# FLYTE-v1.net
KiCad netlist of a schematic drawn in EAGLE
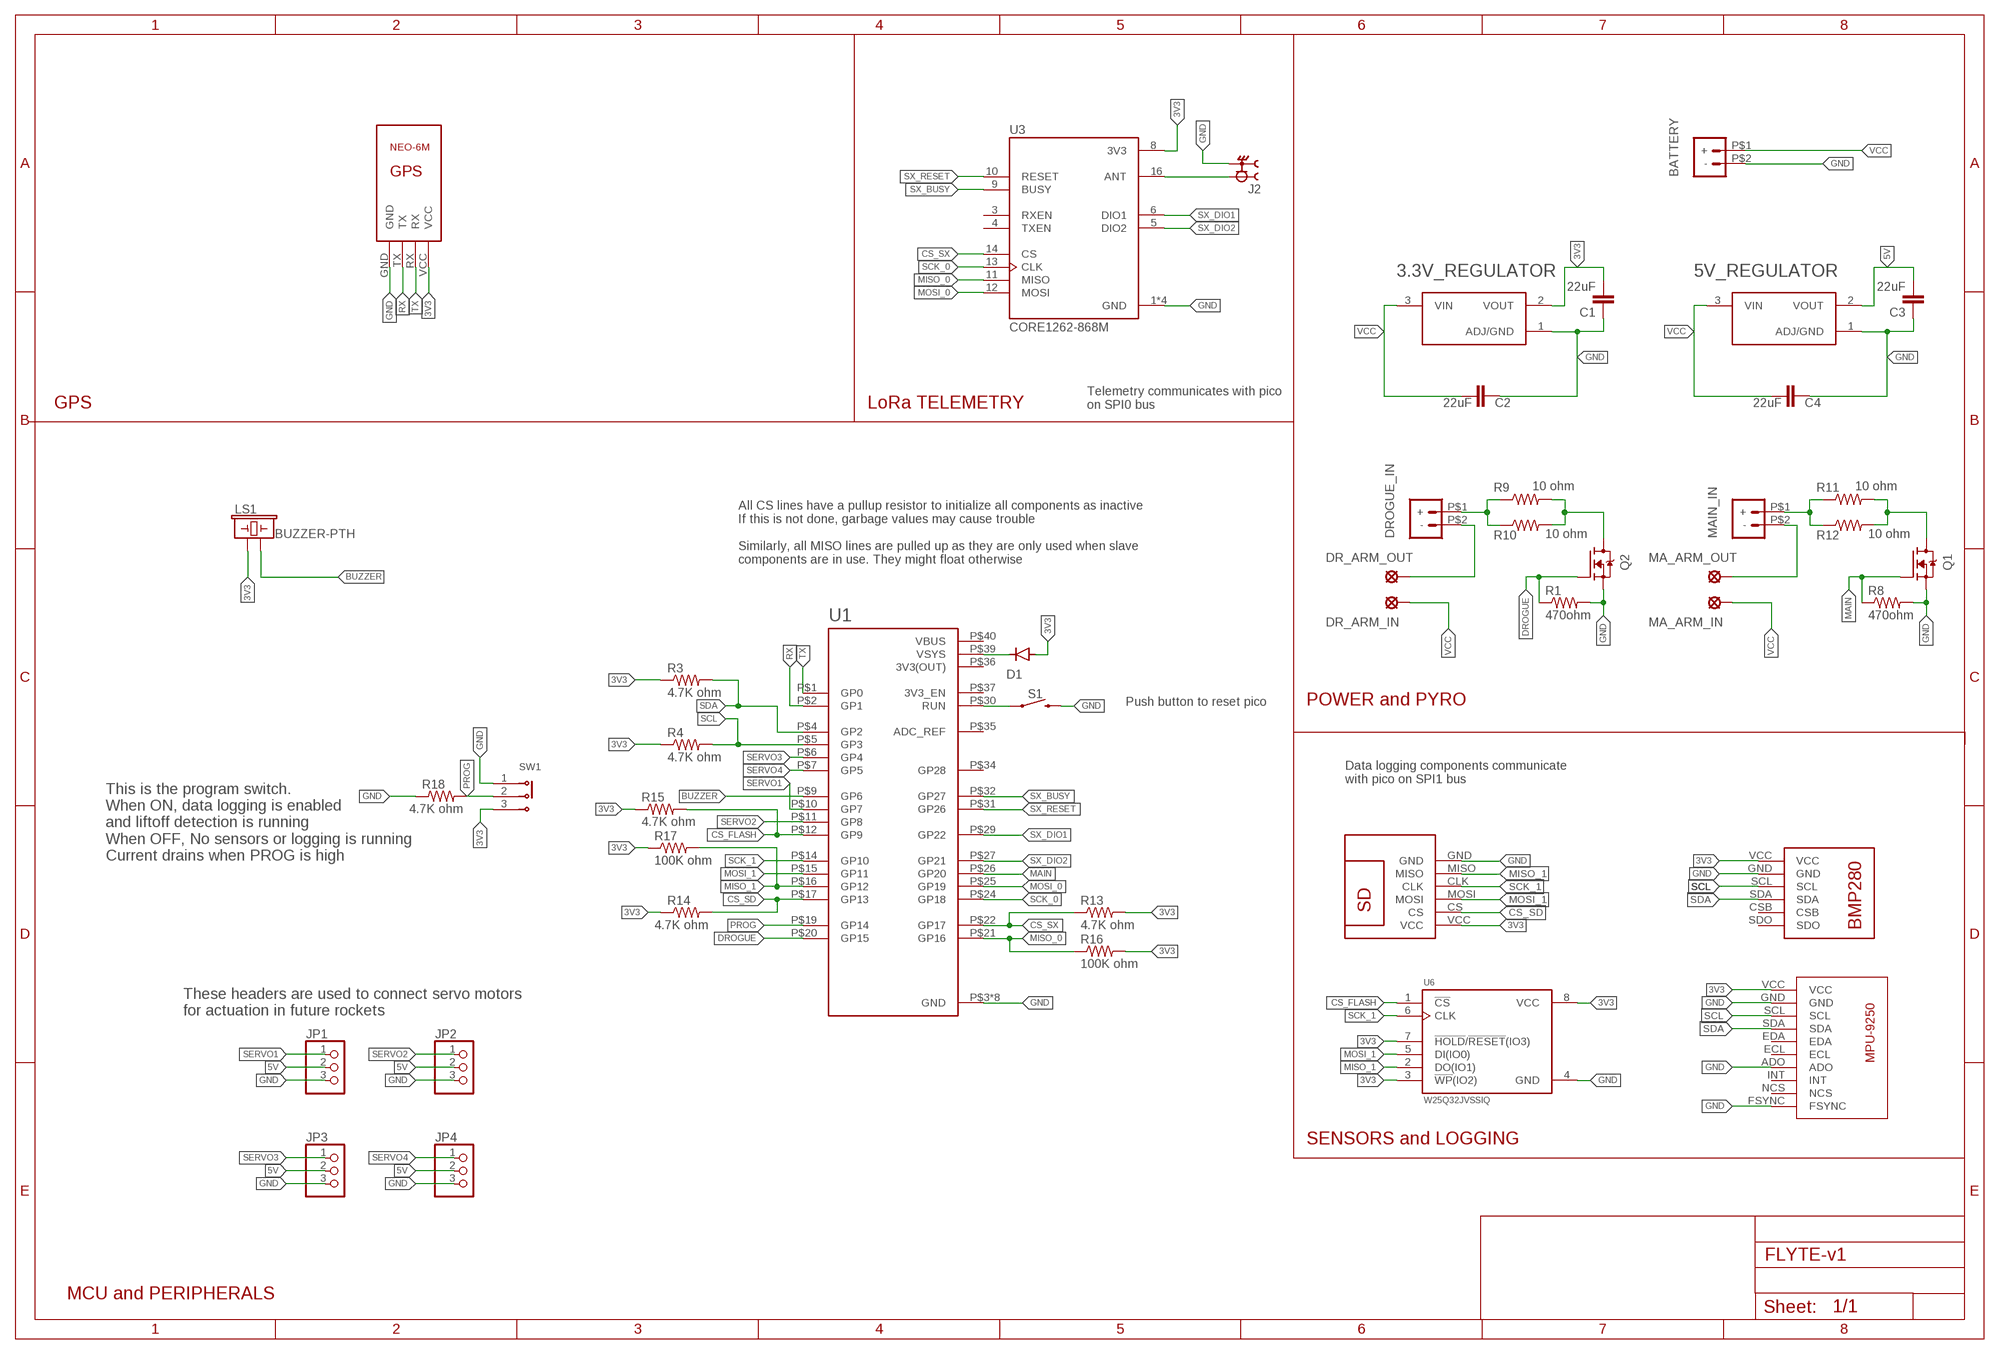
[diagram p0: schematic, sheet 1]

(export (version "E")
  (design (tool "Eeschema 10.0.6"))
  (components
    (comp (ref "3.3V_REGULATOR")
      (value "AMS1117-3.3")
      (footprint "eagle-import:SOT229P700X180-4N")
      (fields (field (name "MF") "Advanced Monolithic Systems"))
      (libsource (lib "eagle-import") (part "AMS1117-3.3"))
    )
    (comp (ref "5V_REGULATOR")
      (value "AMS1117-3.3")
      (footprint "eagle-import:SOT229P700X180-4N")
      (fields (field (name "MF") "Advanced Monolithic Systems"))
      (libsource (lib "eagle-import") (part "AMS1117-3.3"))
    )
    (comp (ref "BATTERY")
      (value "XT30UPB-M")
      (footprint "eagle-import:XT30UPB-M")
      (fields (field (name "MF") "amass"))
      (libsource (lib "eagle-import") (part "XT30UPB-M"))
    )
    (comp (ref "C1")
      (value "22uF")
      (footprint "eagle-import:0805")
      (libsource (lib "eagle-import") (part "22UF-0805-6.3V-20%"))
    )
    (comp (ref "C2")
      (value "22uF")
      (footprint "eagle-import:0805")
      (libsource (lib "eagle-import") (part "22UF-0805-6.3V-20%"))
    )
    (comp (ref "C3")
      (value "22uF")
      (footprint "eagle-import:0805")
      (libsource (lib "eagle-import") (part "22UF-0805-6.3V-20%"))
    )
    (comp (ref "C4")
      (value "22uF")
      (footprint "eagle-import:0805")
      (libsource (lib "eagle-import") (part "22UF-0805-6.3V-20%"))
    )
    (comp (ref "D1")
      (value "1N4004")
      (footprint "eagle-import:DO41-10")
      (libsource (lib "eagle-import") (part "1N4004"))
    )
    (comp (ref "DROGUE_IN")
      (value "XT30UPB-M")
      (footprint "eagle-import:XT30UPB-M")
      (fields (field (name "MF") "amass"))
      (libsource (lib "eagle-import") (part "XT30UPB-M"))
    )
    (comp (ref "DR_ARM_IN")
      (value "LSP10")
      (footprint "eagle-import:LSP10")
      (libsource (lib "eagle-import") (part "LSP10"))
    )
    (comp (ref "DR_ARM_OUT")
      (value "LSP10")
      (footprint "eagle-import:LSP10")
      (libsource (lib "eagle-import") (part "LSP10"))
    )
    (comp (ref "J2")
      (value "CONSMA002")
      (footprint "eagle-import:LINX_CONSMA002")
      (fields (field (name "MF") "Linx"))
      (libsource (lib "eagle-import") (part "CONSMA002"))
    )
    (comp (ref "JP1")
      (value "PINHD-1X3")
      (footprint "eagle-import:1X03")
      (libsource (lib "eagle-import") (part "PINHD-1X3"))
    )
    (comp (ref "JP2")
      (value "PINHD-1X3")
      (footprint "eagle-import:1X03")
      (libsource (lib "eagle-import") (part "PINHD-1X3"))
    )
    (comp (ref "JP3")
      (value "PINHD-1X3")
      (footprint "eagle-import:1X03")
      (libsource (lib "eagle-import") (part "PINHD-1X3"))
    )
    (comp (ref "JP4")
      (value "PINHD-1X3")
      (footprint "eagle-import:1X03")
      (libsource (lib "eagle-import") (part "PINHD-1X3"))
    )
    (comp (ref "LS1")
      (value "BUZZER-PTH")
      (footprint "eagle-import:BUZZER-12MM")
      (libsource (lib "eagle-import") (part "BUZZER-PTH"))
    )
    (comp (ref "MAIN_IN")
      (value "XT30UPB-M")
      (footprint "eagle-import:XT30UPB-M")
      (fields (field (name "MF") "amass"))
      (libsource (lib "eagle-import") (part "XT30UPB-M"))
    )
    (comp (ref "MA_ARM_IN")
      (value "LSP10")
      (footprint "eagle-import:LSP10")
      (libsource (lib "eagle-import") (part "LSP10"))
    )
    (comp (ref "MA_ARM_OUT")
      (value "LSP10")
      (footprint "eagle-import:LSP10")
      (libsource (lib "eagle-import") (part "LSP10"))
    )
    (comp (ref "Q1")
      (value "IRF540NPBF")
      (footprint "eagle-import:TO254P1054X469X1930-3")
      (fields (field (name "MF") "Infineon"))
      (libsource (lib "eagle-import") (part "IRF540NPBF"))
    )
    (comp (ref "Q2")
      (value "IRF540NPBF")
      (footprint "eagle-import:TO254P1054X469X1930-3")
      (fields (field (name "MF") "Infineon"))
      (libsource (lib "eagle-import") (part "IRF540NPBF"))
    )
    (comp (ref "R1")
      (value "470ohm")
      (footprint "eagle-import:R0805")
      (libsource (lib "eagle-import") (part "R-US_R0805"))
    )
    (comp (ref "R3")
      (value "4.7K ohm")
      (footprint "eagle-import:R0805")
      (libsource (lib "eagle-import") (part "R-US_R0805"))
    )
    (comp (ref "R4")
      (value "4.7K ohm")
      (footprint "eagle-import:R0805")
      (libsource (lib "eagle-import") (part "R-US_R0805"))
    )
    (comp (ref "R8")
      (value "470ohm")
      (footprint "eagle-import:R0805")
      (libsource (lib "eagle-import") (part "R-US_R0805"))
    )
    (comp (ref "R9")
      (value "10 ohm")
      (footprint "eagle-import:0207_10")
      (libsource (lib "eagle-import") (part "R-US_0207/10"))
    )
    (comp (ref "R10")
      (value "10 ohm")
      (footprint "eagle-import:0207_10")
      (libsource (lib "eagle-import") (part "R-US_0207/10"))
    )
    (comp (ref "R11")
      (value "10 ohm")
      (footprint "eagle-import:0207_10")
      (libsource (lib "eagle-import") (part "R-US_0207/10"))
    )
    (comp (ref "R12")
      (value "10 ohm")
      (footprint "eagle-import:0207_10")
      (libsource (lib "eagle-import") (part "R-US_0207/10"))
    )
    (comp (ref "R13")
      (value "4.7K ohm")
      (footprint "eagle-import:R0805")
      (libsource (lib "eagle-import") (part "R-US_R0805"))
    )
    (comp (ref "R14")
      (value "4.7K ohm")
      (footprint "eagle-import:R0805")
      (libsource (lib "eagle-import") (part "R-US_R0805"))
    )
    (comp (ref "R15")
      (value "4.7K ohm")
      (footprint "eagle-import:R0805")
      (libsource (lib "eagle-import") (part "R-US_R0805"))
    )
    (comp (ref "R16")
      (value "100K ohm")
      (footprint "eagle-import:R0805")
      (libsource (lib "eagle-import") (part "R-US_R0805"))
    )
    (comp (ref "R17")
      (value "100K ohm")
      (footprint "eagle-import:R0805")
      (libsource (lib "eagle-import") (part "R-US_R0805"))
    )
    (comp (ref "R18")
      (value "4.7K ohm")
      (footprint "eagle-import:R0805")
      (libsource (lib "eagle-import") (part "R-US_R0805"))
    )
    (comp (ref "S1")
      (value "MOMENTARY-SWITCH-SPST-PTH-6.0MM")
      (footprint "eagle-import:TACTILE_SWITCH_PTH_6.0MM")
      (libsource (lib "eagle-import") (part "MOMENTARY-SWITCH-SPST-PTH-6.0MM"))
    )
    (comp (ref "SW1")
      (value "1825159-1")
      (footprint "eagle-import:SW_1825159-1")
      (fields (field (name "MF") "TE Connectivity"))
      (libsource (lib "eagle-import") (part "1825159-1"))
    )
    (comp (ref "U$1")
      (value "BMP280")
      (footprint "eagle-import:BMP280")
      (libsource (lib "eagle-import") (part "BMP280"))
    )
    (comp (ref "U$2")
      (value "GY-9250")
      (footprint "eagle-import:GY-9250")
      (libsource (lib "eagle-import") (part "GY-9250"))
    )
    (comp (ref "U$3")
      (value "SDREADER")
      (footprint "eagle-import:SDREADER")
      (libsource (lib "eagle-import") (part "SDREADER"))
    )
    (comp (ref "U$4")
      (value "NEO-6M")
      (footprint "eagle-import:NEO-6M")
      (libsource (lib "eagle-import") (part "NEO-6M"))
    )
    (comp (ref "U1")
      (value "RASPBERRY_PICO-NO_DEBUG")
      (footprint "eagle-import:PICO-PKG-NO_DEBUG")
      (libsource (lib "eagle-import") (part "RASPBERRY_PICO-NO_DEBUG"))
    )
    (comp (ref "U3")
      (value "CORE1262-868M")
      (footprint "eagle-import:XCVR_CORE1262-868M")
      (fields (field (name "MF") "Waveshare Electronics") (field (name "MP") "Core1262-868M"))
      (libsource (lib "eagle-import") (part "CORE1262-868M"))
    )
    (comp (ref "U6")
      (value "W25Q32JVSSIQ")
      (footprint "eagle-import:SOIC127P790X216-8N")
      (fields (field (name "MF") "Winbond"))
      (libsource (lib "eagle-import") (part "W25Q32JVSSIQ"))
    )
  )
  (nets
    (net (code "1") (name "/3V3(OUT)") (class "Default")
      (node (ref "U1") (pin "P$36") (pinfunction "3V3(OUT)_P$36") (pintype "power_in"))
    )
    (net (code "2") (name "/VBUS") (class "Default")
      (node (ref "U1") (pin "P$40") (pinfunction "VBUS_P$40") (pintype "power_in"))
    )
    (net (code "3") (name "3V3") (class "Default")
      (node (ref "3.3V_REGULATOR") (pin "2") (pinfunction "VOUT_2") (pintype "output"))
      (node (ref "C1") (pin "2") (pinfunction "2_2") (pintype "passive"))
      (node (ref "D1") (pin "A") (pinfunction "A_A") (pintype "passive"))
      (node (ref "LS1") (pin "+") (pinfunction "1_+") (pintype "passive"))
      (node (ref "R13") (pin "2") (pinfunction "2_2") (pintype "passive"))
      (node (ref "R14") (pin "1") (pinfunction "1_1") (pintype "passive"))
      (node (ref "R15") (pin "1") (pinfunction "1_1") (pintype "passive"))
      (node (ref "R16") (pin "2") (pinfunction "2_2") (pintype "passive"))
      (node (ref "R17") (pin "1") (pinfunction "1_1") (pintype "passive"))
      (node (ref "R3") (pin "1") (pinfunction "1_1") (pintype "passive"))
      (node (ref "R4") (pin "1") (pinfunction "1_1") (pintype "passive"))
      (node (ref "SW1") (pin "3") (pinfunction "3_3") (pintype "passive"))
      (node (ref "U$1") (pin "VCC") (pinfunction "VCC_VCC") (pintype "bidirectional"))
      (node (ref "U$2") (pin "VCC") (pinfunction "VCC_VCC") (pintype "bidirectional"))
      (node (ref "U$3") (pin "VCC") (pinfunction "VCC_VCC") (pintype "bidirectional"))
      (node (ref "U$4") (pin "VCC") (pinfunction "VCC_VCC") (pintype "bidirectional"))
      (node (ref "U3") (pin "8") (pinfunction "3V3_8") (pintype "power_in"))
      (node (ref "U6") (pin "3") (pinfunction "~{WP}(IO2)_3") (pintype "bidirectional"))
      (node (ref "U6") (pin "7") (pinfunction "~{HOLD}/~{RESET}(IO3)_7") (pintype "bidirectional"))
      (node (ref "U6") (pin "8") (pinfunction "VCC_8") (pintype "power_in"))
    )
    (net (code "4") (name "5V") (class "Default")
      (node (ref "5V_REGULATOR") (pin "2") (pinfunction "VOUT_2") (pintype "output"))
      (node (ref "C3") (pin "2") (pinfunction "2_2") (pintype "passive"))
      (node (ref "JP1") (pin "2") (pinfunction "2_2") (pintype "passive"))
      (node (ref "JP2") (pin "2") (pinfunction "2_2") (pintype "passive"))
      (node (ref "JP3") (pin "2") (pinfunction "2_2") (pintype "passive"))
      (node (ref "JP4") (pin "2") (pinfunction "2_2") (pintype "passive"))
    )
    (net (code "5") (name "BUZZER") (class "Default")
      (node (ref "LS1") (pin "-") (pinfunction "2_-") (pintype "passive"))
      (node (ref "U1") (pin "P$9") (pinfunction "GP6_P$9") (pintype "bidirectional"))
    )
    (net (code "6") (name "CS_FLASH") (class "Default")
      (node (ref "R15") (pin "2") (pinfunction "2_2") (pintype "passive"))
      (node (ref "U1") (pin "P$12") (pinfunction "GP9_P$12") (pintype "bidirectional"))
      (node (ref "U6") (pin "1") (pinfunction "~{CS}_1") (pintype "input"))
    )
    (net (code "7") (name "CS_SD") (class "Default")
      (node (ref "R14") (pin "2") (pinfunction "2_2") (pintype "passive"))
      (node (ref "U$3") (pin "CS") (pinfunction "CS_CS") (pintype "bidirectional"))
      (node (ref "U1") (pin "P$17") (pinfunction "GP13_P$17") (pintype "bidirectional"))
    )
    (net (code "8") (name "CS_SX") (class "Default")
      (node (ref "R13") (pin "1") (pinfunction "1_1") (pintype "passive"))
      (node (ref "U1") (pin "P$22") (pinfunction "GP17_P$22") (pintype "bidirectional"))
      (node (ref "U3") (pin "14") (pinfunction "CS_14") (pintype "input"))
    )
    (net (code "9") (name "DROGUE") (class "Default")
      (node (ref "Q2") (pin "1") (pinfunction "G_1") (pintype "passive"))
      (node (ref "R1") (pin "1") (pinfunction "1_1") (pintype "passive"))
      (node (ref "U1") (pin "P$20") (pinfunction "GP15_P$20") (pintype "bidirectional"))
    )
    (net (code "10") (name "GND") (class "Default")
      (node (ref "3.3V_REGULATOR") (pin "1") (pinfunction "ADJ/GND_1") (pintype "power_in"))
      (node (ref "5V_REGULATOR") (pin "1") (pinfunction "ADJ/GND_1") (pintype "power_in"))
      (node (ref "BATTERY") (pin "P$2") (pinfunction "-_P$2") (pintype "passive"))
      (node (ref "C1") (pin "1") (pinfunction "1_1") (pintype "passive"))
      (node (ref "C2") (pin "1") (pinfunction "1_1") (pintype "passive"))
      (node (ref "C3") (pin "1") (pinfunction "1_1") (pintype "passive"))
      (node (ref "C4") (pin "1") (pinfunction "1_1") (pintype "passive"))
      (node (ref "J2") (pin "S1") (pinfunction "2_S1") (pintype "passive"))
      (node (ref "J2") (pin "S2") (pinfunction "2_S2") (pintype "passive"))
      (node (ref "J2") (pin "S3") (pinfunction "2_S3") (pintype "passive"))
      (node (ref "J2") (pin "S4") (pinfunction "2_S4") (pintype "passive"))
      (node (ref "JP1") (pin "3") (pinfunction "3_3") (pintype "passive"))
      (node (ref "JP2") (pin "3") (pinfunction "3_3") (pintype "passive"))
      (node (ref "JP3") (pin "3") (pinfunction "3_3") (pintype "passive"))
      (node (ref "JP4") (pin "3") (pinfunction "3_3") (pintype "passive"))
      (node (ref "Q1") (pin "3") (pinfunction "S_3") (pintype "passive"))
      (node (ref "Q2") (pin "3") (pinfunction "S_3") (pintype "passive"))
      (node (ref "R1") (pin "2") (pinfunction "2_2") (pintype "passive"))
      (node (ref "R18") (pin "1") (pinfunction "1_1") (pintype "passive"))
      (node (ref "R8") (pin "2") (pinfunction "2_2") (pintype "passive"))
      (node (ref "S1") (pin "3") (pinfunction "2_3") (pintype "passive"))
      (node (ref "SW1") (pin "1") (pinfunction "1_1") (pintype "passive"))
      (node (ref "U$1") (pin "GND") (pinfunction "GND_GND") (pintype "bidirectional"))
      (node (ref "U$2") (pin "ADO") (pinfunction "ADO_ADO") (pintype "bidirectional"))
      (node (ref "U$2") (pin "FSYNC") (pinfunction "FSYNC_FSYNC") (pintype "bidirectional"))
      (node (ref "U$2") (pin "GND") (pinfunction "GND_GND") (pintype "bidirectional"))
      (node (ref "U$3") (pin "GND") (pinfunction "GND_GND") (pintype "bidirectional"))
      (node (ref "U$4") (pin "GND") (pinfunction "GND_GND") (pintype "bidirectional"))
      (node (ref "U1") (pin "P$13") (pinfunction "GND_P$13") (pintype "power_in"))
      (node (ref "U1") (pin "P$18") (pinfunction "GND_P$18") (pintype "power_in"))
      (node (ref "U1") (pin "P$23") (pinfunction "GND_P$23") (pintype "power_in"))
      (node (ref "U1") (pin "P$28") (pinfunction "GND_P$28") (pintype "power_in"))
      (node (ref "U1") (pin "P$3") (pinfunction "GND_P$3") (pintype "power_in"))
      (node (ref "U1") (pin "P$33") (pinfunction "GND_P$33") (pintype "power_in"))
      (node (ref "U1") (pin "P$38") (pinfunction "GND_P$38") (pintype "power_in"))
      (node (ref "U1") (pin "P$8") (pinfunction "GND_P$8") (pintype "power_in"))
      (node (ref "U3") (pin "1") (pinfunction "GND_1") (pintype "power_in"))
      (node (ref "U3") (pin "15") (pinfunction "GND_15") (pintype "power_in"))
      (node (ref "U3") (pin "2") (pinfunction "GND_2") (pintype "power_in"))
      (node (ref "U3") (pin "7") (pinfunction "GND_7") (pintype "power_in"))
      (node (ref "U6") (pin "4") (pinfunction "GND_4") (pintype "power_in"))
    )
    (net (code "11") (name "MAIN") (class "Default")
      (node (ref "Q1") (pin "1") (pinfunction "G_1") (pintype "passive"))
      (node (ref "R8") (pin "1") (pinfunction "1_1") (pintype "passive"))
      (node (ref "U1") (pin "P$26") (pinfunction "GP20_P$26") (pintype "bidirectional"))
    )
    (net (code "12") (name "MISO_0") (class "Default")
      (node (ref "R16") (pin "1") (pinfunction "1_1") (pintype "passive"))
      (node (ref "U1") (pin "P$21") (pinfunction "GP16_P$21") (pintype "bidirectional"))
      (node (ref "U3") (pin "11") (pinfunction "MISO_11") (pintype "input"))
    )
    (net (code "13") (name "MISO_1") (class "Default")
      (node (ref "R17") (pin "2") (pinfunction "2_2") (pintype "passive"))
      (node (ref "U$3") (pin "MISO") (pinfunction "MISO_MISO") (pintype "bidirectional"))
      (node (ref "U1") (pin "P$16") (pinfunction "GP12_P$16") (pintype "bidirectional"))
      (node (ref "U6") (pin "2") (pinfunction "DO(IO1)_2") (pintype "bidirectional"))
    )
    (net (code "14") (name "MOSI_0") (class "Default")
      (node (ref "U1") (pin "P$25") (pinfunction "GP19_P$25") (pintype "bidirectional"))
      (node (ref "U3") (pin "12") (pinfunction "MOSI_12") (pintype "output"))
    )
    (net (code "15") (name "MOSI_1") (class "Default")
      (node (ref "U$3") (pin "MOSI") (pinfunction "MOSI_MOSI") (pintype "bidirectional"))
      (node (ref "U1") (pin "P$15") (pinfunction "GP11_P$15") (pintype "bidirectional"))
      (node (ref "U6") (pin "5") (pinfunction "DI(IO0)_5") (pintype "bidirectional"))
    )
    (net (code "16") (name "Net-(DROGUE_IN-+)") (class "Default")
      (node (ref "DROGUE_IN") (pin "P$1") (pinfunction "+_P$1") (pintype "passive"))
      (node (ref "R10") (pin "1") (pinfunction "1_1") (pintype "passive"))
      (node (ref "R9") (pin "1") (pinfunction "1_1") (pintype "passive"))
    )
    (net (code "17") (name "Net-(DROGUE_IN--)") (class "Default")
      (node (ref "DROGUE_IN") (pin "P$2") (pinfunction "-_P$2") (pintype "passive"))
      (node (ref "DR_ARM_OUT") (pin "MP") (pinfunction "MP_MP") (pintype "passive"))
    )
    (net (code "18") (name "Net-(MAIN_IN-+)") (class "Default")
      (node (ref "MAIN_IN") (pin "P$1") (pinfunction "+_P$1") (pintype "passive"))
      (node (ref "R11") (pin "1") (pinfunction "1_1") (pintype "passive"))
      (node (ref "R12") (pin "1") (pinfunction "1_1") (pintype "passive"))
    )
    (net (code "19") (name "Net-(MAIN_IN--)") (class "Default")
      (node (ref "MAIN_IN") (pin "P$2") (pinfunction "-_P$2") (pintype "passive"))
      (node (ref "MA_ARM_OUT") (pin "MP") (pinfunction "MP_MP") (pintype "passive"))
    )
    (net (code "20") (name "Net-(Q1-D)") (class "Default")
      (node (ref "Q1") (pin "2") (pinfunction "D_2") (pintype "passive"))
      (node (ref "R11") (pin "2") (pinfunction "2_2") (pintype "passive"))
      (node (ref "R12") (pin "2") (pinfunction "2_2") (pintype "passive"))
    )
    (net (code "21") (name "Net-(Q2-D)") (class "Default")
      (node (ref "Q2") (pin "2") (pinfunction "D_2") (pintype "passive"))
      (node (ref "R10") (pin "2") (pinfunction "2_2") (pintype "passive"))
      (node (ref "R9") (pin "2") (pinfunction "2_2") (pintype "passive"))
    )
    (net (code "22") (name "Net-(U1-RUN)") (class "Default")
      (node (ref "S1") (pin "1") (pinfunction "1_1") (pintype "passive"))
      (node (ref "U1") (pin "P$30") (pinfunction "RUN_P$30") (pintype "input"))
    )
    (net (code "23") (name "Net-(U1-VSYS)") (class "Default")
      (node (ref "D1") (pin "C") (pinfunction "C_C") (pintype "passive"))
      (node (ref "U1") (pin "P$39") (pinfunction "VSYS_P$39") (pintype "power_in"))
    )
    (net (code "24") (name "Net-(U3-ANT)") (class "Default")
      (node (ref "J2") (pin "1") (pinfunction "1_1") (pintype "passive"))
      (node (ref "U3") (pin "16") (pinfunction "ANT_16") (pintype "bidirectional"))
    )
    (net (code "25") (name "PROG") (class "Default")
      (node (ref "R18") (pin "2") (pinfunction "2_2") (pintype "passive"))
      (node (ref "SW1") (pin "2") (pinfunction "2_2") (pintype "passive"))
      (node (ref "U1") (pin "P$19") (pinfunction "GP14_P$19") (pintype "bidirectional"))
    )
    (net (code "26") (name "RX") (class "Default")
      (node (ref "U$4") (pin "TX") (pinfunction "TX_TX") (pintype "bidirectional"))
      (node (ref "U1") (pin "P$2") (pinfunction "GP1_P$2") (pintype "bidirectional"))
    )
    (net (code "27") (name "SCK_0") (class "Default")
      (node (ref "U1") (pin "P$24") (pinfunction "GP18_P$24") (pintype "bidirectional"))
      (node (ref "U3") (pin "13") (pinfunction "CLK_13") (pintype "input"))
    )
    (net (code "28") (name "SCK_1") (class "Default")
      (node (ref "U$3") (pin "CLK") (pinfunction "CLK_CLK") (pintype "bidirectional"))
      (node (ref "U1") (pin "P$14") (pinfunction "GP10_P$14") (pintype "bidirectional"))
      (node (ref "U6") (pin "6") (pinfunction "CLK_6") (pintype "input"))
    )
    (net (code "29") (name "SCL") (class "Default")
      (node (ref "R4") (pin "2") (pinfunction "2_2") (pintype "passive"))
      (node (ref "U$1") (pin "SCL") (pinfunction "SCL_SCL") (pintype "bidirectional"))
      (node (ref "U$2") (pin "SCL") (pinfunction "SCL_SCL") (pintype "bidirectional"))
      (node (ref "U1") (pin "P$5") (pinfunction "GP3_P$5") (pintype "bidirectional"))
    )
    (net (code "30") (name "SDA") (class "Default")
      (node (ref "R3") (pin "2") (pinfunction "2_2") (pintype "passive"))
      (node (ref "U$1") (pin "SDA") (pinfunction "SDA_SDA") (pintype "bidirectional"))
      (node (ref "U$2") (pin "SDA") (pinfunction "SDA_SDA") (pintype "bidirectional"))
      (node (ref "U1") (pin "P$4") (pinfunction "GP2_P$4") (pintype "bidirectional"))
    )
    (net (code "31") (name "SERVO1") (class "Default")
      (node (ref "JP1") (pin "1") (pinfunction "1_1") (pintype "passive"))
      (node (ref "U1") (pin "P$10") (pinfunction "GP7_P$10") (pintype "bidirectional"))
    )
    (net (code "32") (name "SERVO2") (class "Default")
      (node (ref "JP2") (pin "1") (pinfunction "1_1") (pintype "passive"))
      (node (ref "U1") (pin "P$11") (pinfunction "GP8_P$11") (pintype "bidirectional"))
    )
    (net (code "33") (name "SERVO3") (class "Default")
      (node (ref "JP3") (pin "1") (pinfunction "1_1") (pintype "passive"))
      (node (ref "U1") (pin "P$6") (pinfunction "GP4_P$6") (pintype "bidirectional"))
    )
    (net (code "34") (name "SERVO4") (class "Default")
      (node (ref "JP4") (pin "1") (pinfunction "1_1") (pintype "passive"))
      (node (ref "U1") (pin "P$7") (pinfunction "GP5_P$7") (pintype "bidirectional"))
    )
    (net (code "35") (name "SX_BUSY") (class "Default")
      (node (ref "U1") (pin "P$32") (pinfunction "GP27_P$32") (pintype "bidirectional"))
      (node (ref "U3") (pin "9") (pinfunction "BUSY_9") (pintype "input"))
    )
    (net (code "36") (name "SX_DIO1") (class "Default")
      (node (ref "U1") (pin "P$29") (pinfunction "GP22_P$29") (pintype "bidirectional"))
      (node (ref "U3") (pin "6") (pinfunction "DIO1_6") (pintype "bidirectional"))
    )
    (net (code "37") (name "SX_DIO2") (class "Default")
      (node (ref "U1") (pin "P$27") (pinfunction "GP21_P$27") (pintype "bidirectional"))
      (node (ref "U3") (pin "5") (pinfunction "DIO2_5") (pintype "bidirectional"))
    )
    (net (code "38") (name "SX_RESET") (class "Default")
      (node (ref "U1") (pin "P$31") (pinfunction "GP26_P$31") (pintype "bidirectional"))
      (node (ref "U3") (pin "10") (pinfunction "RESET_10") (pintype "input"))
    )
    (net (code "39") (name "TX") (class "Default")
      (node (ref "U$4") (pin "RX") (pinfunction "RX_RX") (pintype "bidirectional"))
      (node (ref "U1") (pin "P$1") (pinfunction "GP0_P$1") (pintype "bidirectional"))
    )
    (net (code "40") (name "VCC") (class "Default")
      (node (ref "3.3V_REGULATOR") (pin "3") (pinfunction "VIN_3") (pintype "input"))
      (node (ref "5V_REGULATOR") (pin "3") (pinfunction "VIN_3") (pintype "input"))
      (node (ref "BATTERY") (pin "P$1") (pinfunction "+_P$1") (pintype "passive"))
      (node (ref "C2") (pin "2") (pinfunction "2_2") (pintype "passive"))
      (node (ref "C4") (pin "2") (pinfunction "2_2") (pintype "passive"))
      (node (ref "DR_ARM_IN") (pin "MP") (pinfunction "MP_MP") (pintype "passive"))
      (node (ref "MA_ARM_IN") (pin "MP") (pinfunction "MP_MP") (pintype "passive"))
    )
    (net (code "41") (name "unconnected-(U$1-PadCSB)") (class "Default")
      (node (ref "U$1") (pin "CSB") (pinfunction "CSB_CSB") (pintype "bidirectional"))
    )
    (net (code "42") (name "unconnected-(U$1-PadSDO)") (class "Default")
      (node (ref "U$1") (pin "SDO") (pinfunction "SDO_SDO") (pintype "bidirectional"))
    )
    (net (code "43") (name "unconnected-(U$2-PadECL)") (class "Default")
      (node (ref "U$2") (pin "ECL") (pinfunction "ECL_ECL") (pintype "bidirectional"))
    )
    (net (code "44") (name "unconnected-(U$2-PadEDA)") (class "Default")
      (node (ref "U$2") (pin "EDA") (pinfunction "EDA_EDA") (pintype "bidirectional"))
    )
    (net (code "45") (name "unconnected-(U$2-PadINT)") (class "Default")
      (node (ref "U$2") (pin "INT") (pinfunction "INT_INT") (pintype "bidirectional"))
    )
    (net (code "46") (name "unconnected-(U$2-PadNCS)") (class "Default")
      (node (ref "U$2") (pin "NCS") (pinfunction "NCS_NCS") (pintype "bidirectional"))
    )
    (net (code "47") (name "unconnected-(U1-3V3_EN-PadP$37)") (class "Default")
      (node (ref "U1") (pin "P$37") (pinfunction "3V3_EN_P$37") (pintype "input"))
    )
    (net (code "48") (name "unconnected-(U1-ADC_REF-PadP$35)") (class "Default")
      (node (ref "U1") (pin "P$35") (pinfunction "ADC_REF_P$35") (pintype "input"))
    )
    (net (code "49") (name "unconnected-(U1-GP28-PadP$34)") (class "Default")
      (node (ref "U1") (pin "P$34") (pinfunction "GP28_P$34") (pintype "bidirectional"))
    )
    (net (code "50") (name "unconnected-(U3-RXEN-Pad3)") (class "Default")
      (node (ref "U3") (pin "3") (pinfunction "RXEN_3") (pintype "input"))
    )
    (net (code "51") (name "unconnected-(U3-TXEN-Pad4)") (class "Default")
      (node (ref "U3") (pin "4") (pinfunction "TXEN_4") (pintype "input"))
    )
  )
)
